# bandpass_40m.net
KiCad netlist of a schematic drawn in EAGLE
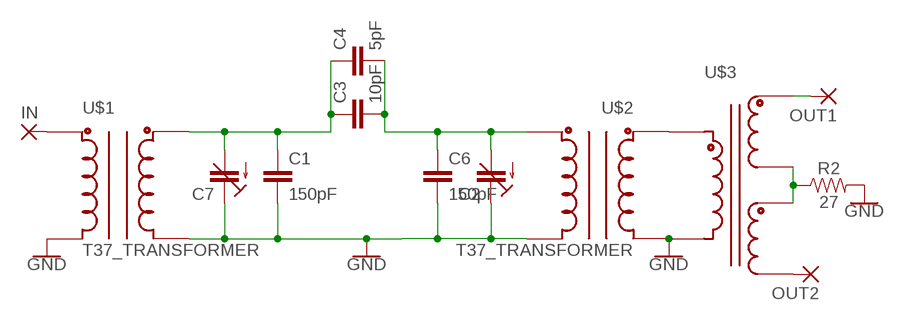
[diagram p0: schematic, sheet 1]

(export (version "E")
  (design (tool "Eeschema 10.0.6"))
  (components
    (comp (ref "C1")
      (value "150pF")
      (footprint "eagle-import:C5B3.5")
      (libsource (lib "eagle-import") (part "C5/3.5"))
    )
    (comp (ref "C2")
      (value "C-TRIMMTZ03")
      (footprint "eagle-import:CTRIMTZ03")
      (libsource (lib "eagle-import") (part "C-TRIMMTZ03"))
    )
    (comp (ref "C3")
      (value "10pF")
      (footprint "eagle-import:C5B3.5")
      (libsource (lib "eagle-import") (part "C5/3.5"))
    )
    (comp (ref "C4")
      (value "5pF")
      (footprint "eagle-import:C5B3.5")
      (libsource (lib "eagle-import") (part "C5/3.5"))
    )
    (comp (ref "C6")
      (value "150pF")
      (footprint "eagle-import:C5B3.5")
      (libsource (lib "eagle-import") (part "C5/3.5"))
    )
    (comp (ref "C7")
      (value "C-TRIMMTZ03")
      (footprint "eagle-import:CTRIMTZ03")
      (libsource (lib "eagle-import") (part "C-TRIMMTZ03"))
    )
    (comp (ref "IN")
      (value "3,17/1,1")
      (footprint "eagle-import:3,17_1,1")
      (libsource (lib "eagle-import") (part "3,17/1,1"))
    )
    (comp (ref "OUT1")
      (value "3,17/1,1")
      (footprint "eagle-import:3,17_1,1")
      (libsource (lib "eagle-import") (part "3,17/1,1"))
    )
    (comp (ref "OUT2")
      (value "3,17/1,1")
      (footprint "eagle-import:3,17_1,1")
      (libsource (lib "eagle-import") (part "3,17/1,1"))
    )
    (comp (ref "R2")
      (value "27")
      (footprint "eagle-import:AXIAL-0.3")
      (libsource (lib "eagle-import") (part "1KOHM-HORIZ-1/4W-1%"))
    )
    (comp (ref "U$1")
      (value "T37_TRANSFORMER")
      (footprint "eagle-import:T37_TRANSFORMER")
      (libsource (lib "eagle-import") (part "T37_TRANSFORMER"))
    )
    (comp (ref "U$2")
      (value "T37_TRANSFORMER")
      (footprint "eagle-import:T37_TRANSFORMER")
      (libsource (lib "eagle-import") (part "T37_TRANSFORMER"))
    )
    (comp (ref "U$3")
      (value "T50_SPLITTER")
      (footprint "eagle-import:T50_SPLITTER")
      (libsource (lib "eagle-import") (part "T50_SPLITTER"))
    )
  )
  (nets
    (net (code "1") (name "GND") (class "Default")
      (node (ref "C1") (pin "2") (pinfunction "2_2") (pintype "passive"))
      (node (ref "C2") (pin "1") (pinfunction "E_1") (pintype "passive"))
      (node (ref "C6") (pin "2") (pinfunction "2_2") (pintype "passive"))
      (node (ref "C7") (pin "1") (pinfunction "E_1") (pintype "passive"))
      (node (ref "R2") (pin "P$2") (pinfunction "2_P$2") (pintype "passive"))
      (node (ref "U$1") (pin "C1A") (pinfunction "C1A_C1A") (pintype "bidirectional"))
      (node (ref "U$1") (pin "C2A") (pinfunction "C2A_C2A") (pintype "bidirectional"))
      (node (ref "U$2") (pin "C1A") (pinfunction "C1A_C1A") (pintype "bidirectional"))
      (node (ref "U$2") (pin "C2A") (pinfunction "C2A_C2A") (pintype "bidirectional"))
      (node (ref "U$3") (pin "C1A") (pinfunction "C1A_C1A") (pintype "bidirectional"))
    )
    (net (code "2") (name "Net-(C2-A)") (class "Default")
      (node (ref "C2") (pin "2") (pinfunction "A_2") (pintype "passive"))
      (node (ref "C3") (pin "2") (pinfunction "2_2") (pintype "passive"))
      (node (ref "C4") (pin "2") (pinfunction "2_2") (pintype "passive"))
      (node (ref "C6") (pin "1") (pinfunction "1_1") (pintype "passive"))
      (node (ref "U$2") (pin "C2B") (pinfunction "C2B_C2B") (pintype "bidirectional"))
    )
    (net (code "3") (name "Net-(C7-A)") (class "Default")
      (node (ref "C1") (pin "1") (pinfunction "1_1") (pintype "passive"))
      (node (ref "C3") (pin "1") (pinfunction "1_1") (pintype "passive"))
      (node (ref "C4") (pin "1") (pinfunction "1_1") (pintype "passive"))
      (node (ref "C7") (pin "2") (pinfunction "A_2") (pintype "passive"))
      (node (ref "U$1") (pin "C2B") (pinfunction "C2B_C2B") (pintype "bidirectional"))
    )
    (net (code "4") (name "Net-(IN-P)") (class "Default")
      (node (ref "IN") (pin "1") (pinfunction "P_1") (pintype "passive"))
      (node (ref "U$1") (pin "C1B") (pinfunction "C1B_C1B") (pintype "bidirectional"))
    )
    (net (code "5") (name "Net-(OUT1-P)") (class "Default")
      (node (ref "OUT1") (pin "1") (pinfunction "P_1") (pintype "passive"))
      (node (ref "U$3") (pin "C3B") (pinfunction "C2B_C3B") (pintype "bidirectional"))
    )
    (net (code "6") (name "Net-(OUT2-P)") (class "Default")
      (node (ref "OUT2") (pin "1") (pinfunction "P_1") (pintype "passive"))
      (node (ref "U$3") (pin "C2B") (pinfunction "C3A_C2B") (pintype "bidirectional"))
    )
    (net (code "7") (name "Net-(R2-1)") (class "Default")
      (node (ref "R2") (pin "P$1") (pinfunction "1_P$1") (pintype "passive"))
      (node (ref "U$3") (pin "C2A") (pinfunction "C3B_C2A") (pintype "bidirectional"))
      (node (ref "U$3") (pin "C3A") (pinfunction "C2A_C3A") (pintype "bidirectional"))
    )
    (net (code "8") (name "Net-(U$2-PadC1B)") (class "Default")
      (node (ref "U$2") (pin "C1B") (pinfunction "C1B_C1B") (pintype "bidirectional"))
      (node (ref "U$3") (pin "C1B") (pinfunction "C1B_C1B") (pintype "bidirectional"))
    )
  )
)
